# NG2092_Connector_A.net
KiCad netlist of a schematic drawn in Altium Designer
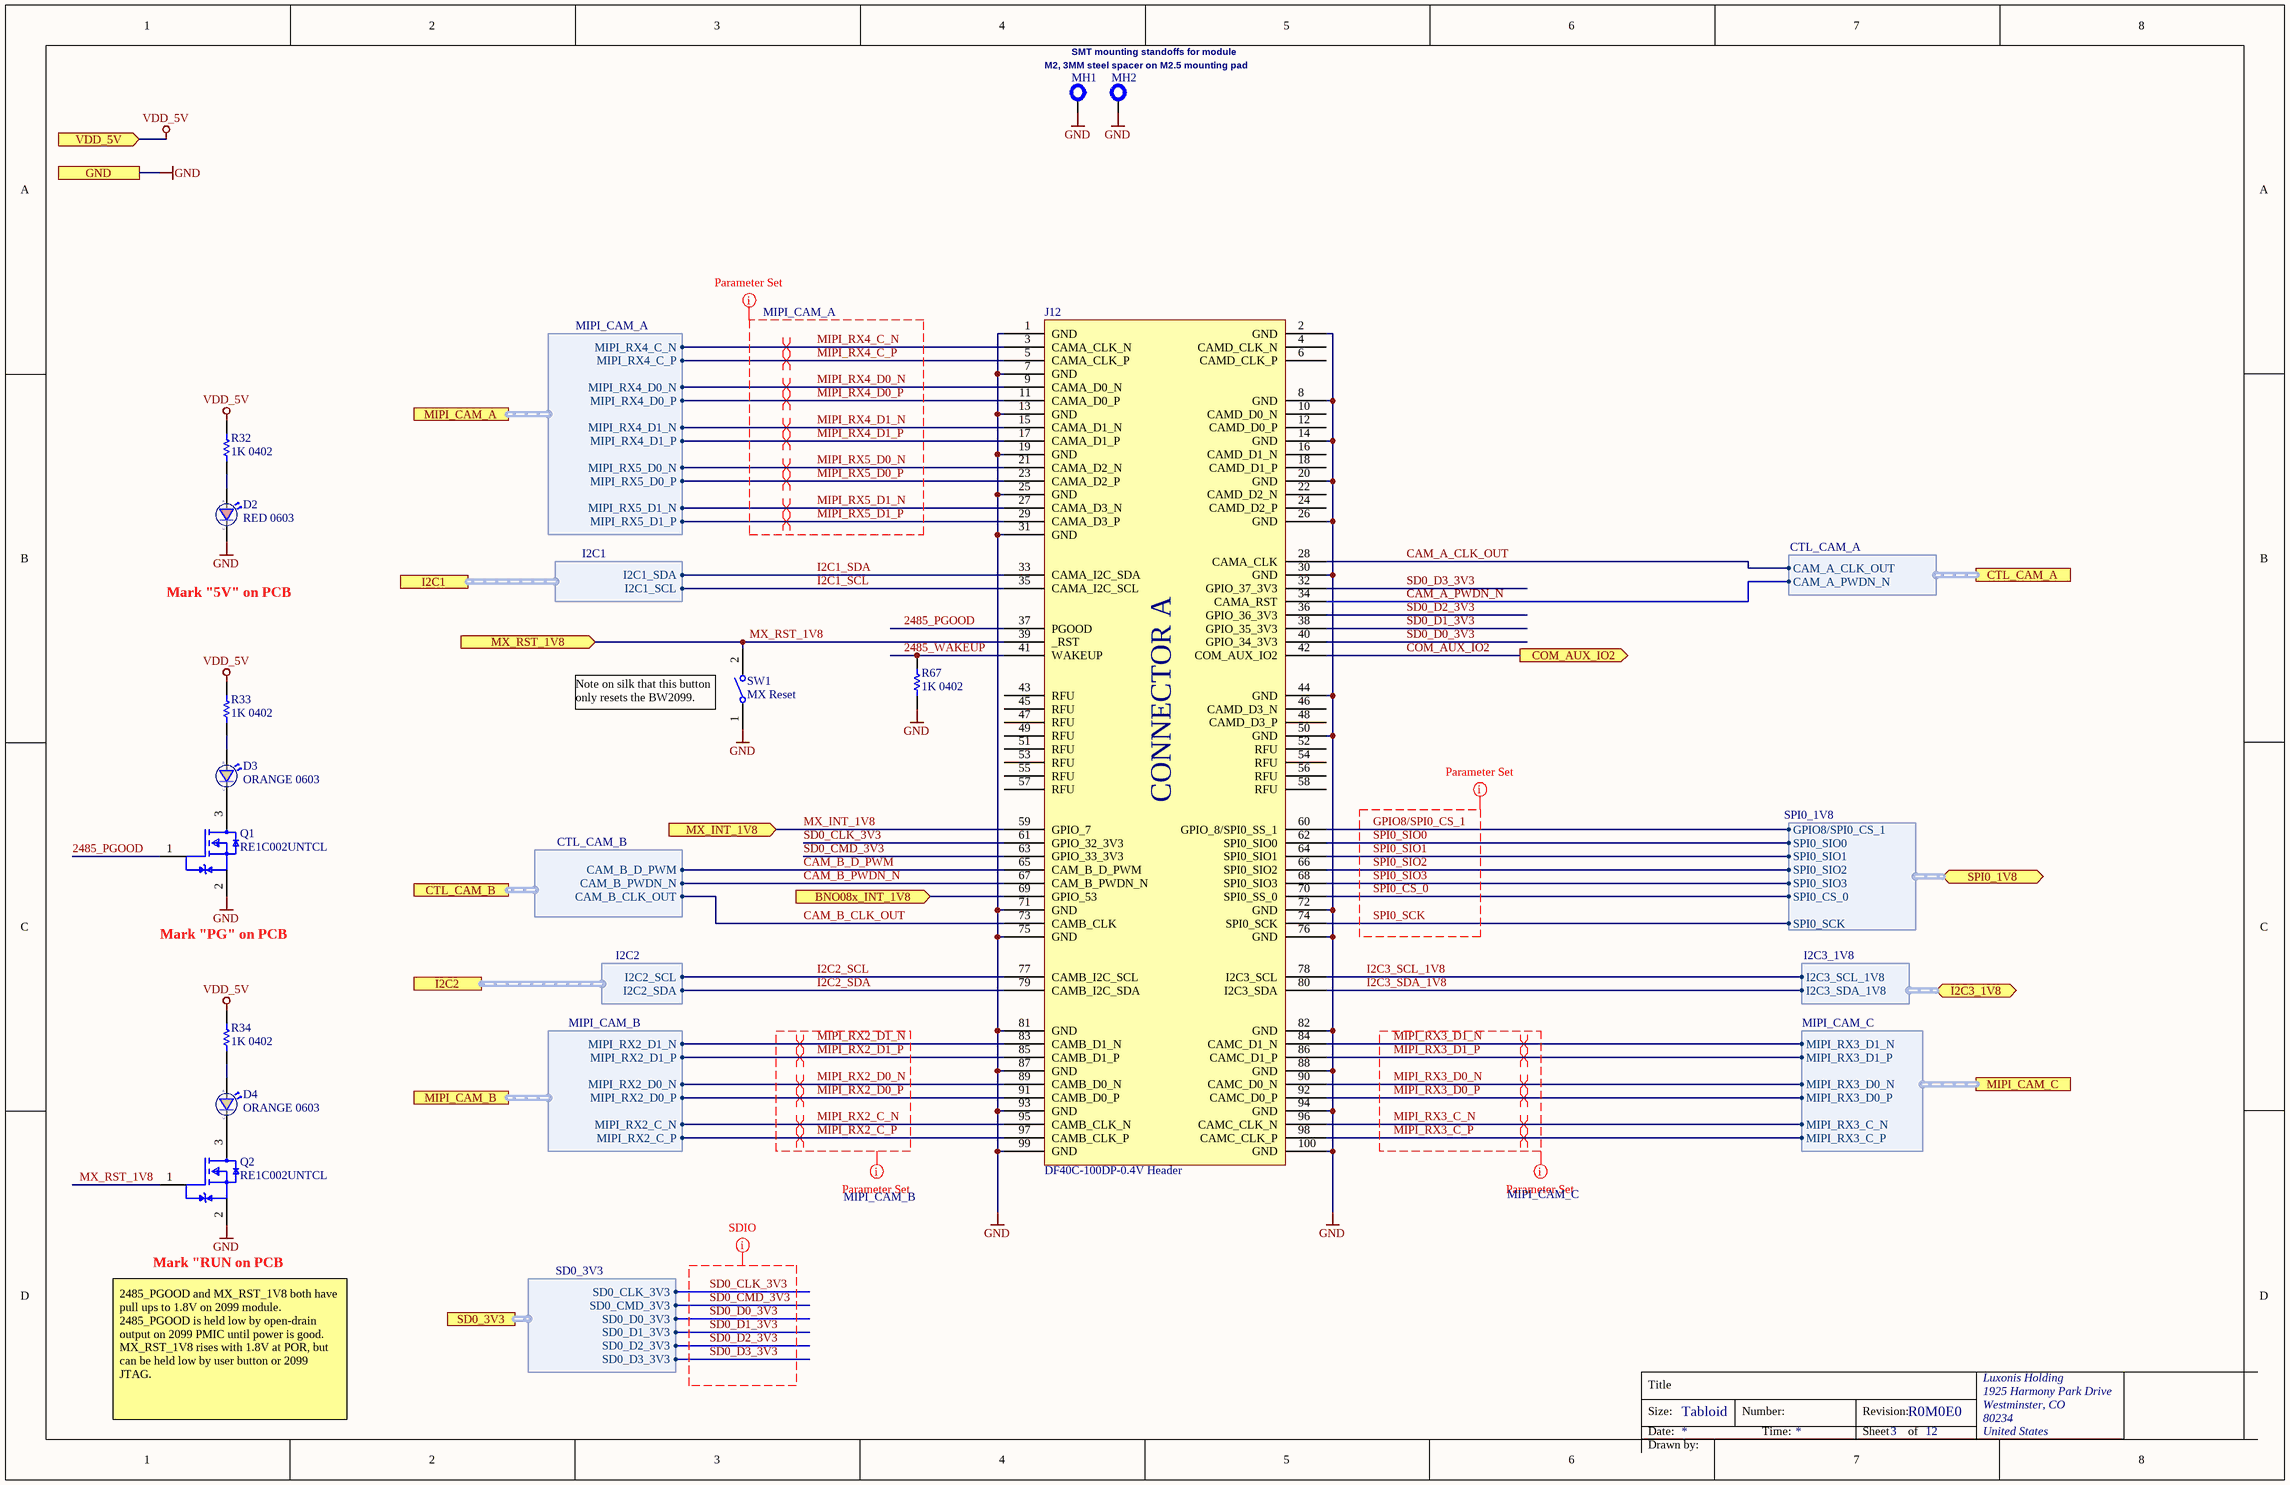
[diagram p0: NG2092_Connector_A.SchDoc]

(export (version "E")
  (design (tool "Eeschema 10.0.6"))
  (components
    (comp (ref "D2")
      (value "RED 0603")
      (footprint "LuxonisMaster:SML_D1xx8W")
      (description "LED RED DIFFUSED 0603 SMD Red 620nm LED Indication - Discrete 2.2V 0603 (1608 Metric)")
      (libsource (lib "LuxonisMaster") (part "SML-D12U8WT86"))
    )
    (comp (ref "D3")
      (value "ORANGE 0603")
      (footprint "LuxonisMaster:SML_D1xx8W")
      (description "LED ORANGE DIFFUSED 0603 SMD Orange 605nm LED Indication - Discrete 2.2V 0603 (1608 Metric)")
      (libsource (lib "LuxonisMaster") (part "SML-D12D8WT86"))
    )
    (comp (ref "D4")
      (value "ORANGE 0603")
      (footprint "LuxonisMaster:SML_D1xx8W")
      (description "LED ORANGE DIFFUSED 0603 SMD Orange 605nm LED Indication - Discrete 2.2V 0603 (1608 Metric)")
      (libsource (lib "LuxonisMaster") (part "SML-D12D8WT86"))
    )
    (comp (ref "J12")
      (value "DF40C-100DP-0.4V Header")
      (footprint "CON_BW2099_A")
      (description "CONN HDR 100POS 0.4MM SMD GOLD BW2099 SYMBOL")
      (libsource (lib "NG2092") (part "DF40C-100DP-0.4V_BW2099_A"))
    )
    (comp (ref "MH1")
      (value "M2, 3MM steel spacer on M2.5 mounting pad")
      (footprint "LuxonisMaster:9774030243R")
      (description "MP ROUND STANDOFF M2X0.4 STEEL 3MM")
      (libsource (lib "LuxonisMaster") (part "9774030243R"))
    )
    (comp (ref "MH2")
      (value "M2, 3MM steel spacer on M2.5 mounting pad")
      (footprint "LuxonisMaster:9774030243R")
      (description "MP ROUND STANDOFF M2X0.4 STEEL 3MM")
      (libsource (lib "LuxonisMaster") (part "9774030243R"))
    )
    (comp (ref "Q1")
      (value "RE1C002UNTCL")
      (footprint "LuxonisMaster:RE1C002UNTCL")
      (description "MOSFET N-CH 20V 0.2A EMT3")
      (libsource (lib "LuxonisMaster") (part "RE1C002UNTCL"))
    )
    (comp (ref "Q2")
      (value "RE1C002UNTCL")
      (footprint "LuxonisMaster:RE1C002UNTCL")
      (description "MOSFET N-CH 20V 0.2A EMT3")
      (libsource (lib "LuxonisMaster") (part "RE1C002UNTCL"))
    )
    (comp (ref "R32")
      (value "1K 0402")
      (footprint "RES_Altium_Vault_Generic:RESC0402(1005)_L")
      (description "RES SMD 1K OHM 1% 1/16W 0402")
      (fields (field (name "TOLERANCE") "1%"))
      (libsource (lib "LuxonisMaster") (part "RC0402FR-071KL"))
    )
    (comp (ref "R33")
      (value "1K 0402")
      (footprint "RES_Altium_Vault_Generic:RESC0402(1005)_L")
      (description "RES SMD 1K OHM 1% 1/16W 0402")
      (fields (field (name "TOLERANCE") "1%"))
      (libsource (lib "LuxonisMaster") (part "RC0402FR-071KL"))
    )
    (comp (ref "R34")
      (value "1K 0402")
      (footprint "RES_Altium_Vault_Generic:RESC0402(1005)_L")
      (description "RES SMD 1K OHM 1% 1/16W 0402")
      (fields (field (name "TOLERANCE") "1%"))
      (libsource (lib "LuxonisMaster") (part "RC0402FR-071KL"))
    )
    (comp (ref "R67")
      (value "1K 0402")
      (footprint "RES_Altium_Vault_Generic:RESC0402(1005)_L")
      (description "RES SMD 1K OHM 1% 1/16W 0402")
      (fields (field (name "TOLERANCE") "1%"))
      (libsource (lib "LuxonisMaster") (part "RC0402FR-071KL"))
    )
    (comp (ref "SW1")
      (value "MX Reset")
      (footprint "OMRON-B3U-3000P_V")
      (libsource (lib "NG2092") (part "CMP-1677-00003-1"))
    )
  )
  (nets
    (net (code "11") (name "/2485_PGOOD") (class "Default")
      (node (ref "J12") (pin "37") (pinfunction "PGOOD_37") (pintype "passive"))
      (node (ref "Q1") (pin "1") (pinfunction "Gate_1") (pintype "passive"))
    )
    (net (code "12") (name "/2485_WAKEUP") (class "Default")
      (node (ref "J12") (pin "41") (pinfunction "WAKEUP_41") (pintype "passive"))
      (node (ref "R67") (pin "2") (pinfunction "2_2") (pintype "passive"))
    )
    (net (code "13") (name "/BNO08x_INT_1V8") (class "Default")
      (node (ref "J12") (pin "69") (pinfunction "GPIO_53_69") (pintype "passive"))
    )
    (net (code "14") (name "/CAM_A_CLK_OUT") (class "Default")
      (node (ref "J12") (pin "28") (pinfunction "CAMA_CLK_28") (pintype "passive"))
    )
    (net (code "15") (name "/CAM_A_PWDN_N") (class "Default")
      (node (ref "J12") (pin "34") (pinfunction "CAMA_RST_34") (pintype "passive"))
    )
    (net (code "16") (name "/CAM_B_CLK_OUT") (class "Default")
      (node (ref "J12") (pin "73") (pinfunction "CAMB_CLK_73") (pintype "passive"))
    )
    (net (code "17") (name "/CAM_B_D_PWM") (class "Default")
      (node (ref "J12") (pin "65") (pinfunction "CAM_B_D_PWM_65") (pintype "passive"))
    )
    (net (code "18") (name "/CAM_B_PWDN_N") (class "Default")
      (node (ref "J12") (pin "67") (pinfunction "CAM_B_PWDN_N_67") (pintype "passive"))
    )
    (net (code "19") (name "/COM_AUX_IO2") (class "Default")
      (node (ref "J12") (pin "42") (pinfunction "COM_AUX_IO2_42") (pintype "passive"))
    )
    (net (code "20") (name "/GPIO8{slash}SPI0_CS_1") (class "Default")
      (node (ref "J12") (pin "60") (pinfunction "GPIO_8/SPI0_SS_1_60") (pintype "passive"))
    )
    (net (code "21") (name "/I2C1_SCL") (class "Default")
      (node (ref "J12") (pin "35") (pinfunction "CAMA_I2C_SCL_35") (pintype "passive"))
    )
    (net (code "22") (name "/I2C1_SDA") (class "Default")
      (node (ref "J12") (pin "33") (pinfunction "CAMA_I2C_SDA_33") (pintype "passive"))
    )
    (net (code "23") (name "/I2C2_SCL") (class "Default")
      (node (ref "J12") (pin "77") (pinfunction "CAMB_I2C_SCL_77") (pintype "passive"))
    )
    (net (code "24") (name "/I2C2_SDA") (class "Default")
      (node (ref "J12") (pin "79") (pinfunction "CAMB_I2C_SDA_79") (pintype "passive"))
    )
    (net (code "25") (name "/I2C3_SCL_1V8") (class "Default")
      (node (ref "J12") (pin "78") (pinfunction "I2C3_SCL_78") (pintype "passive"))
    )
    (net (code "26") (name "/I2C3_SDA_1V8") (class "Default")
      (node (ref "J12") (pin "80") (pinfunction "I2C3_SDA_80") (pintype "passive"))
    )
    (net (code "27") (name "/MIPI_RX2_C_N") (class "Default")
      (node (ref "J12") (pin "95") (pinfunction "CAMB_CLK_N_95") (pintype "passive"))
    )
    (net (code "28") (name "/MIPI_RX2_C_P") (class "Default")
      (node (ref "J12") (pin "97") (pinfunction "CAMB_CLK_P_97") (pintype "passive"))
    )
    (net (code "29") (name "/MIPI_RX2_D0_N") (class "Default")
      (node (ref "J12") (pin "89") (pinfunction "CAMB_D0_N_89") (pintype "passive"))
    )
    (net (code "30") (name "/MIPI_RX2_D0_P") (class "Default")
      (node (ref "J12") (pin "91") (pinfunction "CAMB_D0_P_91") (pintype "passive"))
    )
    (net (code "31") (name "/MIPI_RX2_D1_N") (class "Default")
      (node (ref "J12") (pin "83") (pinfunction "CAMB_D1_N_83") (pintype "passive"))
    )
    (net (code "32") (name "/MIPI_RX2_D1_P") (class "Default")
      (node (ref "J12") (pin "85") (pinfunction "CAMB_D1_P_85") (pintype "passive"))
    )
    (net (code "33") (name "/MIPI_RX3_C_N") (class "Default")
      (node (ref "J12") (pin "96") (pinfunction "CAMC_CLK_N_96") (pintype "passive"))
    )
    (net (code "34") (name "/MIPI_RX3_C_P") (class "Default")
      (node (ref "J12") (pin "98") (pinfunction "CAMC_CLK_P_98") (pintype "passive"))
    )
    (net (code "35") (name "/MIPI_RX3_D0_N") (class "Default")
      (node (ref "J12") (pin "90") (pinfunction "CAMC_D0_N_90") (pintype "passive"))
    )
    (net (code "36") (name "/MIPI_RX3_D0_P") (class "Default")
      (node (ref "J12") (pin "92") (pinfunction "CAMC_D0_P_92") (pintype "passive"))
    )
    (net (code "37") (name "/MIPI_RX3_D1_N") (class "Default")
      (node (ref "J12") (pin "84") (pinfunction "CAMC_D1_N_84") (pintype "passive"))
    )
    (net (code "38") (name "/MIPI_RX3_D1_P") (class "Default")
      (node (ref "J12") (pin "86") (pinfunction "CAMC_D1_P_86") (pintype "passive"))
    )
    (net (code "39") (name "/MIPI_RX4_C_N") (class "Default")
      (node (ref "J12") (pin "3") (pinfunction "CAMA_CLK_N_3") (pintype "passive"))
    )
    (net (code "40") (name "/MIPI_RX4_C_P") (class "Default")
      (node (ref "J12") (pin "5") (pinfunction "CAMA_CLK_P_5") (pintype "passive"))
    )
    (net (code "41") (name "/MIPI_RX4_D0_N") (class "Default")
      (node (ref "J12") (pin "9") (pinfunction "CAMA_D0_N_9") (pintype "passive"))
    )
    (net (code "42") (name "/MIPI_RX4_D0_P") (class "Default")
      (node (ref "J12") (pin "11") (pinfunction "CAMA_D0_P_11") (pintype "passive"))
    )
    (net (code "43") (name "/MIPI_RX4_D1_N") (class "Default")
      (node (ref "J12") (pin "15") (pinfunction "CAMA_D1_N_15") (pintype "passive"))
    )
    (net (code "44") (name "/MIPI_RX4_D1_P") (class "Default")
      (node (ref "J12") (pin "17") (pinfunction "CAMA_D1_P_17") (pintype "passive"))
    )
    (net (code "45") (name "/MIPI_RX5_D0_N") (class "Default")
      (node (ref "J12") (pin "21") (pinfunction "CAMA_D2_N_21") (pintype "passive"))
    )
    (net (code "46") (name "/MIPI_RX5_D0_P") (class "Default")
      (node (ref "J12") (pin "23") (pinfunction "CAMA_D2_P_23") (pintype "passive"))
    )
    (net (code "47") (name "/MIPI_RX5_D1_N") (class "Default")
      (node (ref "J12") (pin "27") (pinfunction "CAMA_D3_N_27") (pintype "passive"))
    )
    (net (code "48") (name "/MIPI_RX5_D1_P") (class "Default")
      (node (ref "J12") (pin "29") (pinfunction "CAMA_D3_P_29") (pintype "passive"))
    )
    (net (code "49") (name "/MX_INT_1V8") (class "Default")
      (node (ref "J12") (pin "59") (pinfunction "GPIO_7_59") (pintype "passive"))
    )
    (net (code "50") (name "/MX_RST_1V8") (class "Default")
      (node (ref "J12") (pin "39") (pinfunction "_RST_39") (pintype "passive"))
      (node (ref "Q2") (pin "1") (pinfunction "Gate_1") (pintype "passive"))
      (node (ref "SW1") (pin "2") (pinfunction "2_2") (pintype "passive"))
    )
    (net (code "51") (name "/SD0_CLK_3V3") (class "Default")
      (node (ref "J12") (pin "61") (pinfunction "GPIO_32_3V3_61") (pintype "passive"))
    )
    (net (code "52") (name "/SD0_CMD_3V3") (class "Default")
      (node (ref "J12") (pin "63") (pinfunction "GPIO_33_3V3_63") (pintype "passive"))
    )
    (net (code "53") (name "/SD0_D0_3V3") (class "Default")
      (node (ref "J12") (pin "40") (pinfunction "GPIO_34_3V3_40") (pintype "passive"))
    )
    (net (code "54") (name "/SD0_D1_3V3") (class "Default")
      (node (ref "J12") (pin "38") (pinfunction "GPIO_35_3V3_38") (pintype "passive"))
    )
    (net (code "55") (name "/SD0_D2_3V3") (class "Default")
      (node (ref "J12") (pin "36") (pinfunction "GPIO_36_3V3_36") (pintype "passive"))
    )
    (net (code "56") (name "/SD0_D3_3V3") (class "Default")
      (node (ref "J12") (pin "32") (pinfunction "GPIO_37_3V3_32") (pintype "passive"))
    )
    (net (code "57") (name "/SPI0_CS_0") (class "Default")
      (node (ref "J12") (pin "70") (pinfunction "SPI0_SS_0_70") (pintype "passive"))
    )
    (net (code "58") (name "/SPI0_SCK") (class "Default")
      (node (ref "J12") (pin "74") (pinfunction "SPI0_SCK_74") (pintype "passive"))
    )
    (net (code "59") (name "/SPI0_SIO0") (class "Default")
      (node (ref "J12") (pin "62") (pinfunction "SPI0_SIO0_62") (pintype "passive"))
    )
    (net (code "60") (name "/SPI0_SIO1") (class "Default")
      (node (ref "J12") (pin "64") (pinfunction "SPI0_SIO1_64") (pintype "passive"))
    )
    (net (code "61") (name "/SPI0_SIO2") (class "Default")
      (node (ref "J12") (pin "66") (pinfunction "SPI0_SIO2_66") (pintype "passive"))
    )
    (net (code "62") (name "/SPI0_SIO3") (class "Default")
      (node (ref "J12") (pin "68") (pinfunction "SPI0_SIO3_68") (pintype "passive"))
    )
    (net (code "73") (name "GND") (class "Default")
      (node (ref "D2") (pin "1") (pinfunction "C_1") (pintype "passive"))
      (node (ref "J12") (pin "1") (pinfunction "GND_1") (pintype "passive"))
      (node (ref "J12") (pin "100") (pinfunction "GND_100") (pintype "passive"))
      (node (ref "J12") (pin "13") (pinfunction "GND_13") (pintype "passive"))
      (node (ref "J12") (pin "14") (pinfunction "GND_14") (pintype "passive"))
      (node (ref "J12") (pin "19") (pinfunction "GND_19") (pintype "passive"))
      (node (ref "J12") (pin "2") (pinfunction "GND_2") (pintype "passive"))
      (node (ref "J12") (pin "20") (pinfunction "GND_20") (pintype "passive"))
      (node (ref "J12") (pin "25") (pinfunction "GND_25") (pintype "passive"))
      (node (ref "J12") (pin "26") (pinfunction "GND_26") (pintype "passive"))
      (node (ref "J12") (pin "30") (pinfunction "GND_30") (pintype "passive"))
      (node (ref "J12") (pin "31") (pinfunction "GND_31") (pintype "passive"))
      (node (ref "J12") (pin "44") (pinfunction "GND_44") (pintype "passive"))
      (node (ref "J12") (pin "50") (pinfunction "GND_50") (pintype "passive"))
      (node (ref "J12") (pin "7") (pinfunction "GND_7") (pintype "passive"))
      (node (ref "J12") (pin "71") (pinfunction "GND_71") (pintype "passive"))
      (node (ref "J12") (pin "72") (pinfunction "GND_72") (pintype "passive"))
      (node (ref "J12") (pin "75") (pinfunction "GND_75") (pintype "passive"))
      (node (ref "J12") (pin "76") (pinfunction "GND_76") (pintype "passive"))
      (node (ref "J12") (pin "8") (pinfunction "GND_8") (pintype "passive"))
      (node (ref "J12") (pin "81") (pinfunction "GND_81") (pintype "passive"))
      (node (ref "J12") (pin "82") (pinfunction "GND_82") (pintype "passive"))
      (node (ref "J12") (pin "87") (pinfunction "GND_87") (pintype "passive"))
      (node (ref "J12") (pin "88") (pinfunction "GND_88") (pintype "passive"))
      (node (ref "J12") (pin "93") (pinfunction "GND_93") (pintype "passive"))
      (node (ref "J12") (pin "94") (pinfunction "GND_94") (pintype "passive"))
      (node (ref "J12") (pin "99") (pinfunction "GND_99") (pintype "passive"))
      (node (ref "MH1") (pin "1") (pintype "passive"))
      (node (ref "MH2") (pin "1") (pintype "passive"))
      (node (ref "Q1") (pin "2") (pinfunction "Source_2") (pintype "passive"))
      (node (ref "Q2") (pin "2") (pinfunction "Source_2") (pintype "passive"))
      (node (ref "R67") (pin "1") (pinfunction "1_1") (pintype "passive"))
      (node (ref "SW1") (pin "1") (pinfunction "1_1") (pintype "passive"))
    )
    (net (code "74") (name "Net-(D2-A)") (class "Default")
      (node (ref "D2") (pin "2") (pinfunction "A_2") (pintype "passive"))
      (node (ref "R32") (pin "1") (pinfunction "1_1") (pintype "passive"))
    )
    (net (code "75") (name "Net-(D3-A)") (class "Default")
      (node (ref "D3") (pin "2") (pinfunction "A_2") (pintype "passive"))
      (node (ref "R33") (pin "1") (pinfunction "1_1") (pintype "passive"))
    )
    (net (code "76") (name "Net-(D3-C)") (class "Default")
      (node (ref "D3") (pin "1") (pinfunction "C_1") (pintype "passive"))
      (node (ref "Q1") (pin "3") (pinfunction "Drain_3") (pintype "passive"))
    )
    (net (code "77") (name "Net-(D4-A)") (class "Default")
      (node (ref "D4") (pin "2") (pinfunction "A_2") (pintype "passive"))
      (node (ref "R34") (pin "1") (pinfunction "1_1") (pintype "passive"))
    )
    (net (code "78") (name "Net-(D4-C)") (class "Default")
      (node (ref "D4") (pin "1") (pinfunction "C_1") (pintype "passive"))
      (node (ref "Q2") (pin "3") (pinfunction "Drain_3") (pintype "passive"))
    )
    (net (code "79") (name "VDD_5V") (class "Default")
      (node (ref "R32") (pin "2") (pinfunction "2_2") (pintype "passive"))
      (node (ref "R33") (pin "2") (pinfunction "2_2") (pintype "passive"))
      (node (ref "R34") (pin "2") (pinfunction "2_2") (pintype "passive"))
    )
    (net (code "80") (name "unconnected-(J12-CAMD_CLK_N-Pad4)") (class "Default")
      (node (ref "J12") (pin "4") (pinfunction "CAMD_CLK_N_4") (pintype "passive"))
    )
    (net (code "81") (name "unconnected-(J12-CAMD_CLK_P-Pad6)") (class "Default")
      (node (ref "J12") (pin "6") (pinfunction "CAMD_CLK_P_6") (pintype "passive"))
    )
    (net (code "82") (name "unconnected-(J12-CAMD_D0_N-Pad10)") (class "Default")
      (node (ref "J12") (pin "10") (pinfunction "CAMD_D0_N_10") (pintype "passive"))
    )
    (net (code "83") (name "unconnected-(J12-CAMD_D0_P-Pad12)") (class "Default")
      (node (ref "J12") (pin "12") (pinfunction "CAMD_D0_P_12") (pintype "passive"))
    )
    (net (code "84") (name "unconnected-(J12-CAMD_D1_N-Pad16)") (class "Default")
      (node (ref "J12") (pin "16") (pinfunction "CAMD_D1_N_16") (pintype "passive"))
    )
    (net (code "85") (name "unconnected-(J12-CAMD_D1_P-Pad18)") (class "Default")
      (node (ref "J12") (pin "18") (pinfunction "CAMD_D1_P_18") (pintype "passive"))
    )
    (net (code "86") (name "unconnected-(J12-CAMD_D2_N-Pad22)") (class "Default")
      (node (ref "J12") (pin "22") (pinfunction "CAMD_D2_N_22") (pintype "passive"))
    )
    (net (code "87") (name "unconnected-(J12-CAMD_D2_P-Pad24)") (class "Default")
      (node (ref "J12") (pin "24") (pinfunction "CAMD_D2_P_24") (pintype "passive"))
    )
    (net (code "88") (name "unconnected-(J12-CAMD_D3_N-Pad46)") (class "Default")
      (node (ref "J12") (pin "46") (pinfunction "CAMD_D3_N_46") (pintype "passive"))
    )
    (net (code "89") (name "unconnected-(J12-CAMD_D3_P-Pad48)") (class "Default")
      (node (ref "J12") (pin "48") (pinfunction "CAMD_D3_P_48") (pintype "passive"))
    )
    (net (code "90") (name "unconnected-(J12-RFU-Pad43)") (class "Default")
      (node (ref "J12") (pin "43") (pinfunction "RFU_43") (pintype "passive"))
    )
    (net (code "91") (name "unconnected-(J12-RFU-Pad45)") (class "Default")
      (node (ref "J12") (pin "45") (pinfunction "RFU_45") (pintype "passive"))
    )
    (net (code "92") (name "unconnected-(J12-RFU-Pad47)") (class "Default")
      (node (ref "J12") (pin "47") (pinfunction "RFU_47") (pintype "passive"))
    )
    (net (code "93") (name "unconnected-(J12-RFU-Pad49)") (class "Default")
      (node (ref "J12") (pin "49") (pinfunction "RFU_49") (pintype "passive"))
    )
    (net (code "94") (name "unconnected-(J12-RFU-Pad51)") (class "Default")
      (node (ref "J12") (pin "51") (pinfunction "RFU_51") (pintype "passive"))
    )
    (net (code "95") (name "unconnected-(J12-RFU-Pad52)") (class "Default")
      (node (ref "J12") (pin "52") (pinfunction "RFU_52") (pintype "passive"))
    )
    (net (code "96") (name "unconnected-(J12-RFU-Pad53)") (class "Default")
      (node (ref "J12") (pin "53") (pinfunction "RFU_53") (pintype "passive"))
    )
    (net (code "97") (name "unconnected-(J12-RFU-Pad54)") (class "Default")
      (node (ref "J12") (pin "54") (pinfunction "RFU_54") (pintype "passive"))
    )
    (net (code "98") (name "unconnected-(J12-RFU-Pad55)") (class "Default")
      (node (ref "J12") (pin "55") (pinfunction "RFU_55") (pintype "passive"))
    )
    (net (code "99") (name "unconnected-(J12-RFU-Pad56)") (class "Default")
      (node (ref "J12") (pin "56") (pinfunction "RFU_56") (pintype "passive"))
    )
    (net (code "100") (name "unconnected-(J12-RFU-Pad57)") (class "Default")
      (node (ref "J12") (pin "57") (pinfunction "RFU_57") (pintype "passive"))
    )
    (net (code "101") (name "unconnected-(J12-RFU-Pad58)") (class "Default")
      (node (ref "J12") (pin "58") (pinfunction "RFU_58") (pintype "passive"))
    )
  )
)
